# UM_V2_ItsyBitsy.net
KiCad netlist of a schematic drawn in EAGLE
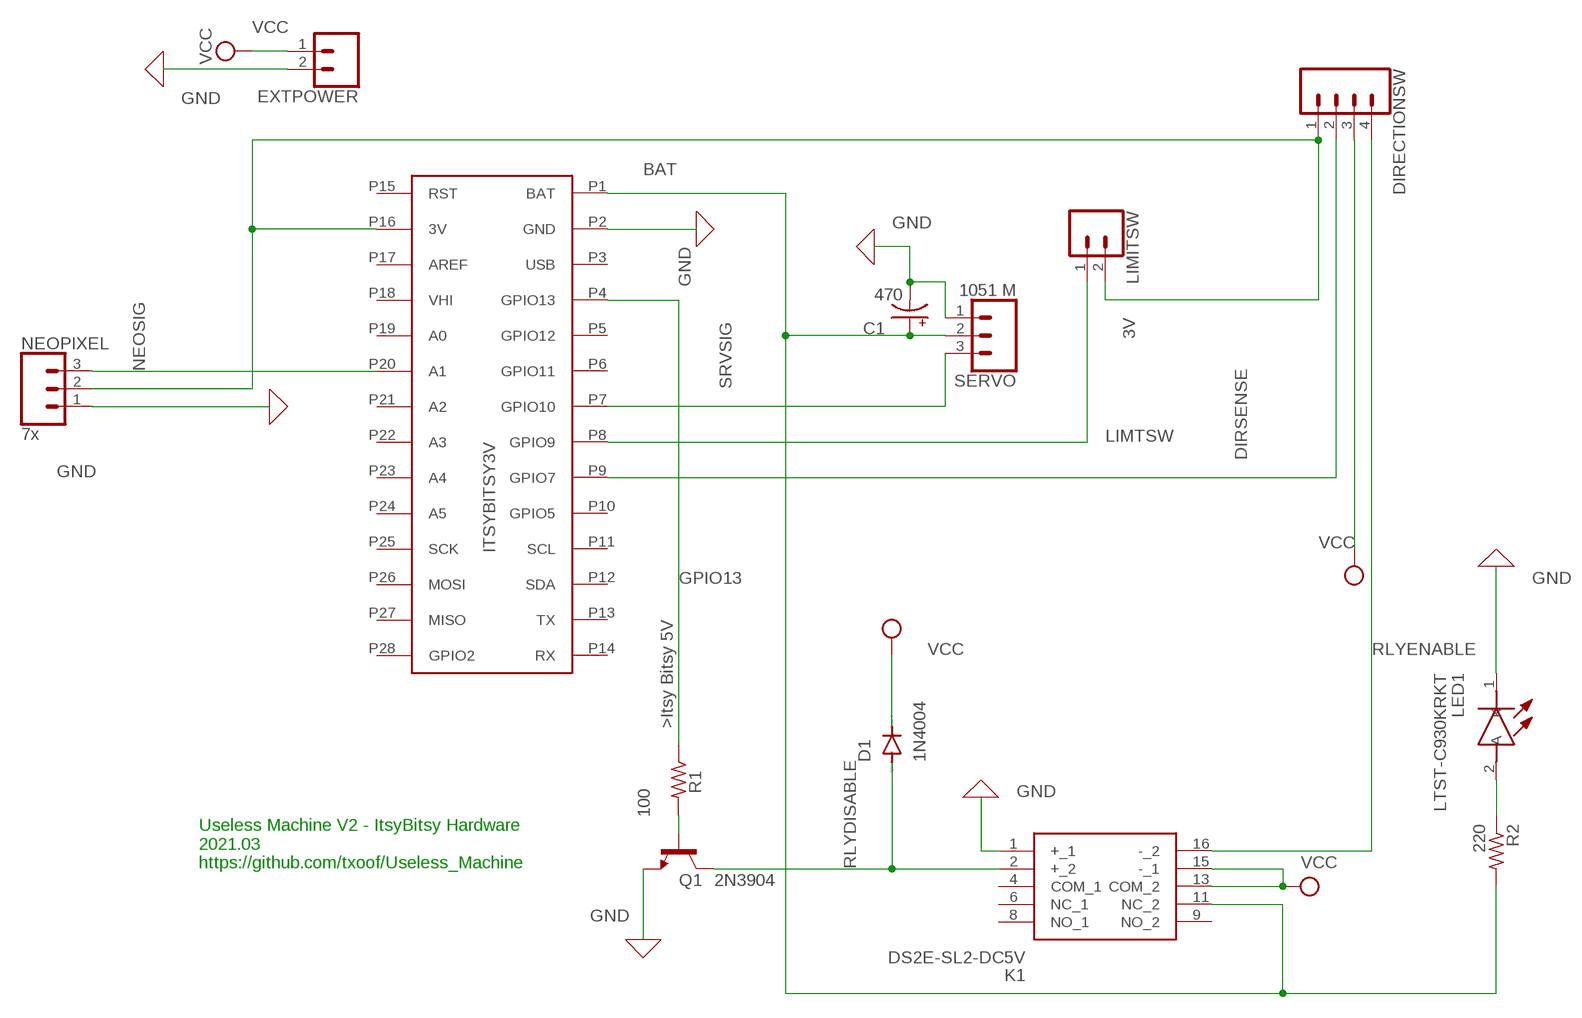
[diagram p0: schematic, sheet 1]

(export (version "E")
  (design (tool "Eeschema 10.0.6"))
  (components
    (comp (ref "C1")
      (value "470")
      (footprint "eagle-import:E2,5-6E")
      (libsource (lib "eagle-import") (part "CPOL-USE2,5-6E"))
    )
    (comp (ref "D1")
      (value "1N4004")
      (footprint "eagle-import:DO41-10")
      (libsource (lib "eagle-import") (part "1N4004"))
    )
    (comp (ref "DIRECTIONSW")
      (value "Direction Sw")
      (footprint "eagle-import:MOLEX-1X4")
      (libsource (lib "eagle-import") (part "CONN_04POLAR"))
    )
    (comp (ref "EXTPOWER")
      (value "Limit Sw")
      (footprint "eagle-import:MOLEX-1X2")
      (libsource (lib "eagle-import") (part "CONN_02POLAR"))
    )
    (comp (ref "K1")
      (value "DS2E-SL2-DC5V")
      (footprint "eagle-import:DS2ESL2DC5V")
      (libsource (lib "eagle-import") (part "DS2E-SL2-DC5V"))
    )
    (comp (ref "LED1")
      (value "LTST-C930KRKT")
      (footprint "eagle-import:LTSTC930KRKT")
      (fields
        (field (name "MOUSER_PART_NUMBER") "859-LTST-C930KRKT")
        (field (name "RS_PART_NUMBER") "1689768")
      )
      (libsource (lib "eagle-import") (part "LTST-C930KRKT"))
    )
    (comp (ref "LIMITSW")
      (value "Limit Sw")
      (footprint "eagle-import:MOLEX-1X2")
      (libsource (lib "eagle-import") (part "CONN_02POLAR"))
    )
    (comp (ref "NEOPIXEL")
      (value "7x")
      (footprint "eagle-import:MOLEX-1X3")
      (libsource (lib "eagle-import") (part "CONN_03POLAR"))
    )
    (comp (ref "Q1")
      (value "2N3904")
      (footprint "eagle-import:TO92-CBE")
      (libsource (lib "eagle-import") (part "-NPN-TO92-CBEMPS2222A"))
    )
    (comp (ref "R1")
      (value "100")
      (footprint "eagle-import:M1206")
      (libsource (lib "eagle-import") (part "R-US_M1206"))
    )
    (comp (ref "R2")
      (value "220")
      (footprint "eagle-import:M1206")
      (libsource (lib "eagle-import") (part "R-US_M1206"))
    )
    (comp (ref "SERVO")
      (value "1051 M")
      (footprint "eagle-import:MOLEX-1X3")
      (libsource (lib "eagle-import") (part "CONN_03POLAR"))
    )
    (comp (ref "U$1")
      (value "ITSYBITSY3V")
      (footprint "eagle-import:ITSYBITSY3V")
      (libsource (lib "eagle-import") (part "ITSYBITSY3V"))
    )
  )
  (nets
    (net (code "1") (name "/3V") (class "Default")
      (node (ref "DIRECTIONSW") (pin "1") (pinfunction "1_1") (pintype "passive"))
      (node (ref "LIMITSW") (pin "2") (pinfunction "2_2") (pintype "passive"))
      (node (ref "NEOPIXEL") (pin "2") (pinfunction "2_2") (pintype "passive"))
      (node (ref "U$1") (pin "P16") (pinfunction "3V_P16") (pintype "power_in"))
    )
    (net (code "2") (name "/BAT") (class "Default")
      (node (ref "C1") (pin "+") (pinfunction "+_+") (pintype "passive"))
      (node (ref "K1") (pin "11") (pinfunction "NC_2_11") (pintype "bidirectional"))
      (node (ref "R2") (pin "2") (pinfunction "2_2") (pintype "passive"))
      (node (ref "SERVO") (pin "2") (pinfunction "2_2") (pintype "passive"))
      (node (ref "U$1") (pin "P1") (pinfunction "BAT_P1") (pintype "power_in"))
    )
    (net (code "3") (name "/DIRSENSE") (class "Default")
      (node (ref "DIRECTIONSW") (pin "2") (pinfunction "2_2") (pintype "passive"))
      (node (ref "U$1") (pin "P9") (pinfunction "GPIO7_P9") (pintype "bidirectional"))
    )
    (net (code "4") (name "/GPIO13") (class "Default")
      (node (ref "R1") (pin "1") (pinfunction "1_1") (pintype "passive"))
      (node (ref "U$1") (pin "P4") (pinfunction "GPIO13_P4") (pintype "bidirectional"))
    )
    (net (code "5") (name "/LIMTSW") (class "Default")
      (node (ref "LIMITSW") (pin "1") (pinfunction "1_1") (pintype "passive"))
      (node (ref "U$1") (pin "P8") (pinfunction "GPIO9_P8") (pintype "bidirectional"))
    )
    (net (code "6") (name "/NEOSIG") (class "Default")
      (node (ref "NEOPIXEL") (pin "3") (pinfunction "3_3") (pintype "passive"))
      (node (ref "U$1") (pin "P20") (pinfunction "A1_P20") (pintype "bidirectional"))
    )
    (net (code "7") (name "/RLYDISABLE") (class "Default")
      (node (ref "D1") (pin "A") (pinfunction "A_A") (pintype "passive"))
      (node (ref "K1") (pin "2") (pinfunction "+_2_2") (pintype "bidirectional"))
      (node (ref "Q1") (pin "C") (pinfunction "C_C") (pintype "passive"))
    )
    (net (code "8") (name "/RLYENABLE") (class "Default")
      (node (ref "DIRECTIONSW") (pin "4") (pinfunction "4_4") (pintype "passive"))
      (node (ref "K1") (pin "16") (pinfunction "-_2_16") (pintype "bidirectional"))
    )
    (net (code "9") (name "/SRVSIG") (class "Default")
      (node (ref "SERVO") (pin "3") (pinfunction "3_3") (pintype "passive"))
      (node (ref "U$1") (pin "P7") (pinfunction "GPIO10_P7") (pintype "bidirectional"))
    )
    (net (code "10") (name "/USB") (class "Default")
      (node (ref "U$1") (pin "P3") (pinfunction "USB_P3") (pintype "power_in"))
    )
    (net (code "11") (name "/VHI") (class "Default")
      (node (ref "U$1") (pin "P18") (pinfunction "VHI_P18") (pintype "power_in"))
    )
    (net (code "12") (name "GND") (class "Default")
      (node (ref "C1") (pin "-") (pinfunction "-_-") (pintype "passive"))
      (node (ref "EXTPOWER") (pin "2") (pinfunction "2_2") (pintype "passive"))
      (node (ref "K1") (pin "1") (pinfunction "+_1_1") (pintype "bidirectional"))
      (node (ref "LED1") (pin "1") (pinfunction "K_1") (pintype "bidirectional"))
      (node (ref "NEOPIXEL") (pin "1") (pinfunction "1_1") (pintype "passive"))
      (node (ref "Q1") (pin "E") (pinfunction "E_E") (pintype "passive"))
      (node (ref "SERVO") (pin "1") (pinfunction "1_1") (pintype "passive"))
      (node (ref "U$1") (pin "P2") (pinfunction "GND_P2") (pintype "power_in"))
    )
    (net (code "13") (name "Net-(LED1-A)") (class "Default")
      (node (ref "LED1") (pin "2") (pinfunction "A_2") (pintype "bidirectional"))
      (node (ref "R2") (pin "1") (pinfunction "1_1") (pintype "passive"))
    )
    (net (code "14") (name "Net-(Q1-PadB)") (class "Default")
      (node (ref "Q1") (pin "B") (pinfunction "B_B") (pintype "passive"))
      (node (ref "R1") (pin "2") (pinfunction "2_2") (pintype "passive"))
    )
    (net (code "15") (name "VCC") (class "Default")
      (node (ref "D1") (pin "C") (pinfunction "C_C") (pintype "passive"))
      (node (ref "DIRECTIONSW") (pin "3") (pinfunction "3_3") (pintype "passive"))
      (node (ref "EXTPOWER") (pin "1") (pinfunction "1_1") (pintype "passive"))
      (node (ref "K1") (pin "13") (pinfunction "COM_2_13") (pintype "bidirectional"))
      (node (ref "K1") (pin "15") (pinfunction "-_1_15") (pintype "bidirectional"))
    )
    (net (code "16") (name "unconnected-(K1-COM_1-Pad4)") (class "Default")
      (node (ref "K1") (pin "4") (pinfunction "COM_1_4") (pintype "bidirectional"))
    )
    (net (code "17") (name "unconnected-(K1-NC_1-Pad6)") (class "Default")
      (node (ref "K1") (pin "6") (pinfunction "NC_1_6") (pintype "bidirectional"))
    )
    (net (code "18") (name "unconnected-(K1-NO_1-Pad8)") (class "Default")
      (node (ref "K1") (pin "8") (pinfunction "NO_1_8") (pintype "bidirectional"))
    )
    (net (code "19") (name "unconnected-(K1-NO_2-Pad9)") (class "Default")
      (node (ref "K1") (pin "9") (pinfunction "NO_2_9") (pintype "bidirectional"))
    )
    (net (code "20") (name "unconnected-(U$1-A0-PadP19)") (class "Default")
      (node (ref "U$1") (pin "P19") (pinfunction "A0_P19") (pintype "bidirectional"))
    )
    (net (code "21") (name "unconnected-(U$1-A2-PadP21)") (class "Default")
      (node (ref "U$1") (pin "P21") (pinfunction "A2_P21") (pintype "bidirectional"))
    )
    (net (code "22") (name "unconnected-(U$1-A3-PadP22)") (class "Default")
      (node (ref "U$1") (pin "P22") (pinfunction "A3_P22") (pintype "bidirectional"))
    )
    (net (code "23") (name "unconnected-(U$1-A4-PadP23)") (class "Default")
      (node (ref "U$1") (pin "P23") (pinfunction "A4_P23") (pintype "bidirectional"))
    )
    (net (code "24") (name "unconnected-(U$1-A5-PadP24)") (class "Default")
      (node (ref "U$1") (pin "P24") (pinfunction "A5_P24") (pintype "bidirectional"))
    )
    (net (code "25") (name "unconnected-(U$1-AREF-PadP17)") (class "Default")
      (node (ref "U$1") (pin "P17") (pinfunction "AREF_P17") (pintype "bidirectional"))
    )
    (net (code "26") (name "unconnected-(U$1-GPIO2-PadP28)") (class "Default")
      (node (ref "U$1") (pin "P28") (pinfunction "GPIO2_P28") (pintype "bidirectional"))
    )
    (net (code "27") (name "unconnected-(U$1-GPIO5-PadP10)") (class "Default")
      (node (ref "U$1") (pin "P10") (pinfunction "GPIO5_P10") (pintype "bidirectional"))
    )
    (net (code "28") (name "unconnected-(U$1-GPIO11-PadP6)") (class "Default")
      (node (ref "U$1") (pin "P6") (pinfunction "GPIO11_P6") (pintype "bidirectional"))
    )
    (net (code "29") (name "unconnected-(U$1-GPIO12-PadP5)") (class "Default")
      (node (ref "U$1") (pin "P5") (pinfunction "GPIO12_P5") (pintype "bidirectional"))
    )
    (net (code "30") (name "unconnected-(U$1-MISO-PadP27)") (class "Default")
      (node (ref "U$1") (pin "P27") (pinfunction "MISO_P27") (pintype "bidirectional"))
    )
    (net (code "31") (name "unconnected-(U$1-MOSI-PadP26)") (class "Default")
      (node (ref "U$1") (pin "P26") (pinfunction "MOSI_P26") (pintype "bidirectional"))
    )
    (net (code "32") (name "unconnected-(U$1-RST-PadP15)") (class "Default")
      (node (ref "U$1") (pin "P15") (pinfunction "RST_P15") (pintype "bidirectional"))
    )
    (net (code "33") (name "unconnected-(U$1-RX-PadP14)") (class "Default")
      (node (ref "U$1") (pin "P14") (pinfunction "RX_P14") (pintype "bidirectional"))
    )
    (net (code "34") (name "unconnected-(U$1-SCK-PadP25)") (class "Default")
      (node (ref "U$1") (pin "P25") (pinfunction "SCK_P25") (pintype "bidirectional"))
    )
    (net (code "35") (name "unconnected-(U$1-SCL-PadP11)") (class "Default")
      (node (ref "U$1") (pin "P11") (pinfunction "SCL_P11") (pintype "bidirectional"))
    )
    (net (code "36") (name "unconnected-(U$1-SDA-PadP12)") (class "Default")
      (node (ref "U$1") (pin "P12") (pinfunction "SDA_P12") (pintype "bidirectional"))
    )
    (net (code "37") (name "unconnected-(U$1-TX-PadP13)") (class "Default")
      (node (ref "U$1") (pin "P13") (pinfunction "TX_P13") (pintype "bidirectional"))
    )
  )
)
